# SCH_NFC_PCB_Business_Card_v3.net
KiCad netlist of a schematic drawn in EasyEDA
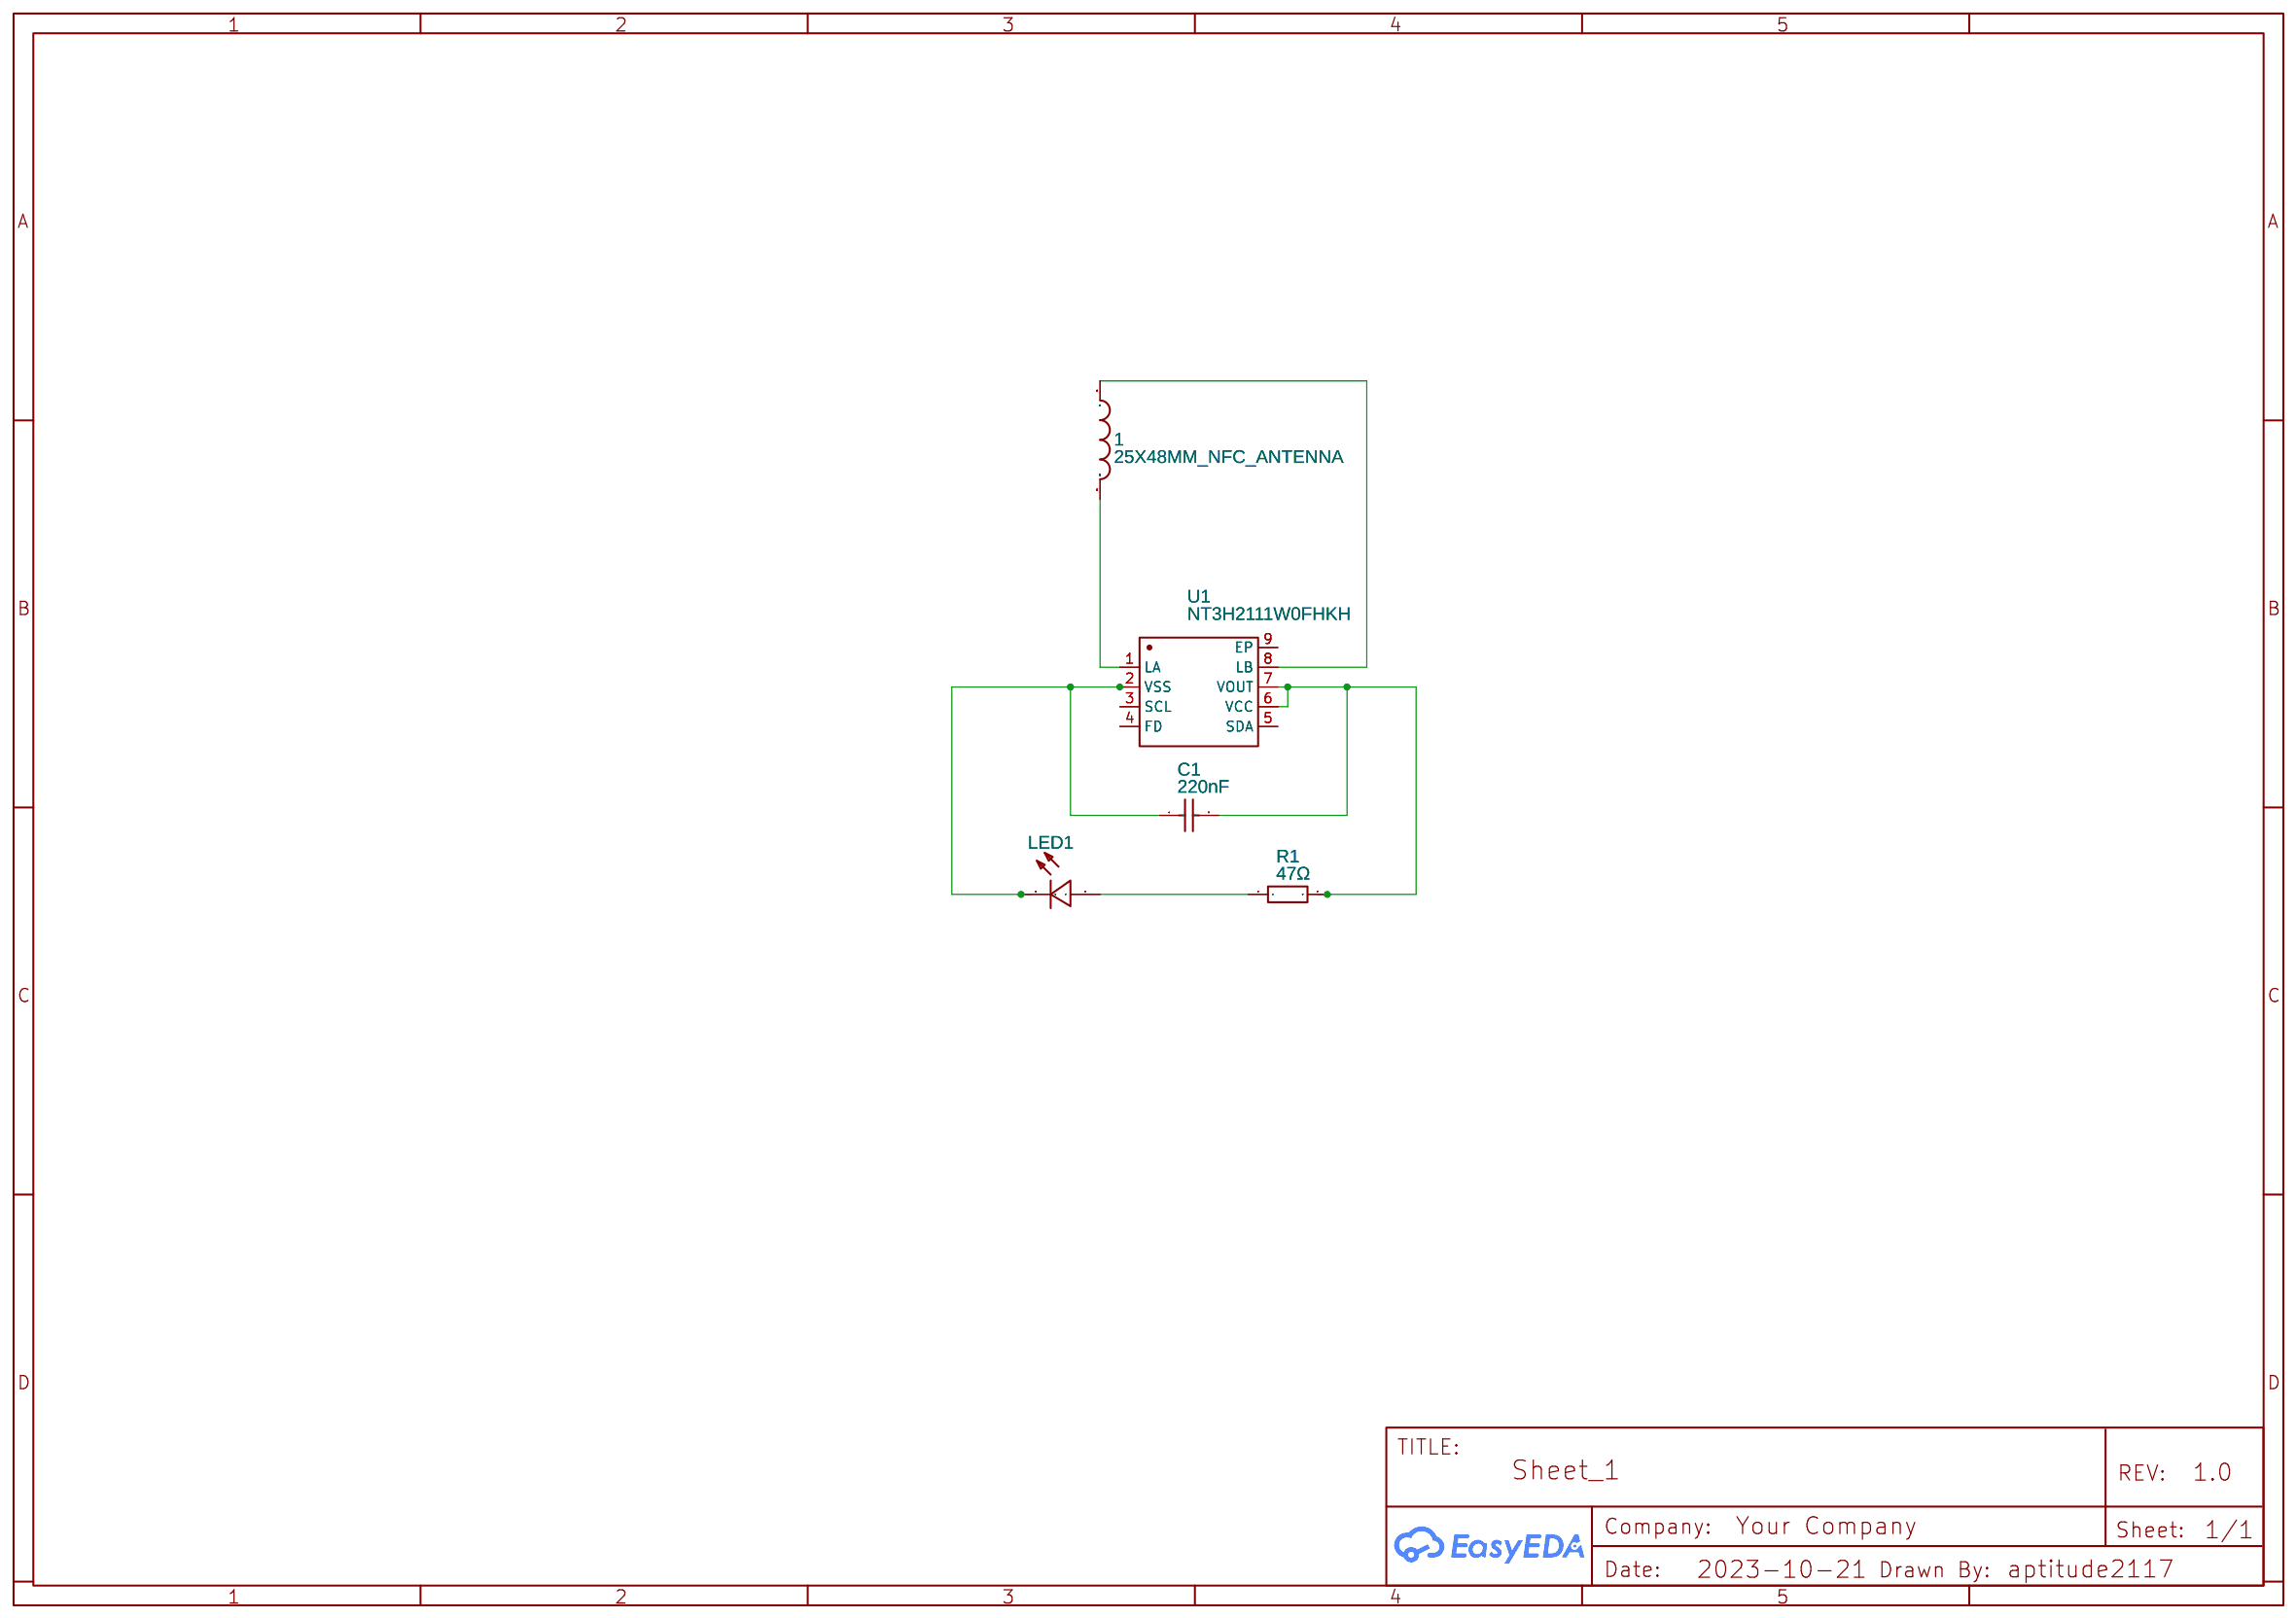
[diagram p0: schematic sheet]

(export (version "E")
  (design (tool "Eeschema 10.0.6"))
  (components
    (comp (ref "1") (value "25X48MM_NFC_ANTENNA") (libsource (lib "") (part "25X48MM_NFC_ANTENNA")))
    (comp (ref "C1")
      (value "220nF")
      (fields
        (field (name "Manufacturer Part") "CL10B224KA8NNNC")
        (field (name "Manufacturer") "SAMSUNG(三星)")
      )
      (libsource (lib "") (part "CL10B224KA8NNNC"))
    )
    (comp (ref "LED1")
      (value "17-21UYOC/S530-A2/TR8")
      (fields (field (name "Manufacturer") "EVERLIGHT(亿光)"))
      (libsource (lib "") (part "17-21UYOC/S530-A2/TR8"))
    )
    (comp (ref "R1")
      (value "47Ω")
      (fields
        (field (name "Manufacturer Part") "0603WAF470JT5E")
        (field (name "Manufacturer") "UNI-ROYAL(厚声)")
      )
      (libsource (lib "") (part "0603WAF470JT5E"))
    )
    (comp (ref "U1")
      (value "NT3H2111W0FHKH")
      (fields (field (name "Manufacturer") "NXP(恩智浦)"))
      (libsource (lib "") (part "NT3H2111W0FHKH"))
    )
  )
  (nets
    (net (code "1") (name "Net-(LED1-Pad1)") (class "Default")
      (node (ref "LED1") (pin "1") (pinfunction "1_1") (pintype "unspecified"))
      (node (ref "R1") (pin "1") (pinfunction "1_1") (pintype "input"))
    )
    (net (code "2") (name "Net-(U1-LA)") (class "Default")
      (node (ref "1") (pin "P$2") (pinfunction "P$2_P$2") (pintype "bidirectional"))
      (node (ref "U1") (pin "1") (pinfunction "LA_1") (pintype "unspecified"))
    )
    (net (code "3") (name "Net-(U1-LB)") (class "Default")
      (node (ref "1") (pin "P$1") (pinfunction "P$1_P$1") (pintype "bidirectional"))
      (node (ref "U1") (pin "8") (pinfunction "LB_8") (pintype "unspecified"))
    )
    (net (code "4") (name "Net-(U1-VCC)") (class "Default")
      (node (ref "C1") (pin "2") (pinfunction "2_2") (pintype "input"))
      (node (ref "R1") (pin "2") (pinfunction "2_2") (pintype "input"))
      (node (ref "U1") (pin "6") (pinfunction "VCC_6") (pintype "unspecified"))
      (node (ref "U1") (pin "7") (pinfunction "VOUT_7") (pintype "unspecified"))
    )
    (net (code "5") (name "Net-(U1-VSS)") (class "Default")
      (node (ref "C1") (pin "1") (pinfunction "1_1") (pintype "input"))
      (node (ref "LED1") (pin "2") (pinfunction "2_2") (pintype "unspecified"))
      (node (ref "U1") (pin "2") (pinfunction "VSS_2") (pintype "unspecified"))
    )
    (net (code "6") (name "unconnected-(U1-EP-Pad9)") (class "Default")
      (node (ref "U1") (pin "9") (pinfunction "EP_9") (pintype "unspecified"))
    )
    (net (code "7") (name "unconnected-(U1-FD-Pad4)") (class "Default")
      (node (ref "U1") (pin "4") (pinfunction "FD_4") (pintype "unspecified"))
    )
    (net (code "8") (name "unconnected-(U1-SCL-Pad3)") (class "Default")
      (node (ref "U1") (pin "3") (pinfunction "SCL_3") (pintype "unspecified"))
    )
    (net (code "9") (name "unconnected-(U1-SDA-Pad5)") (class "Default")
      (node (ref "U1") (pin "5") (pinfunction "SDA_5") (pintype "unspecified"))
    )
  )
)
